# main.net
KiCad netlist of a schematic drawn in Altium Designer
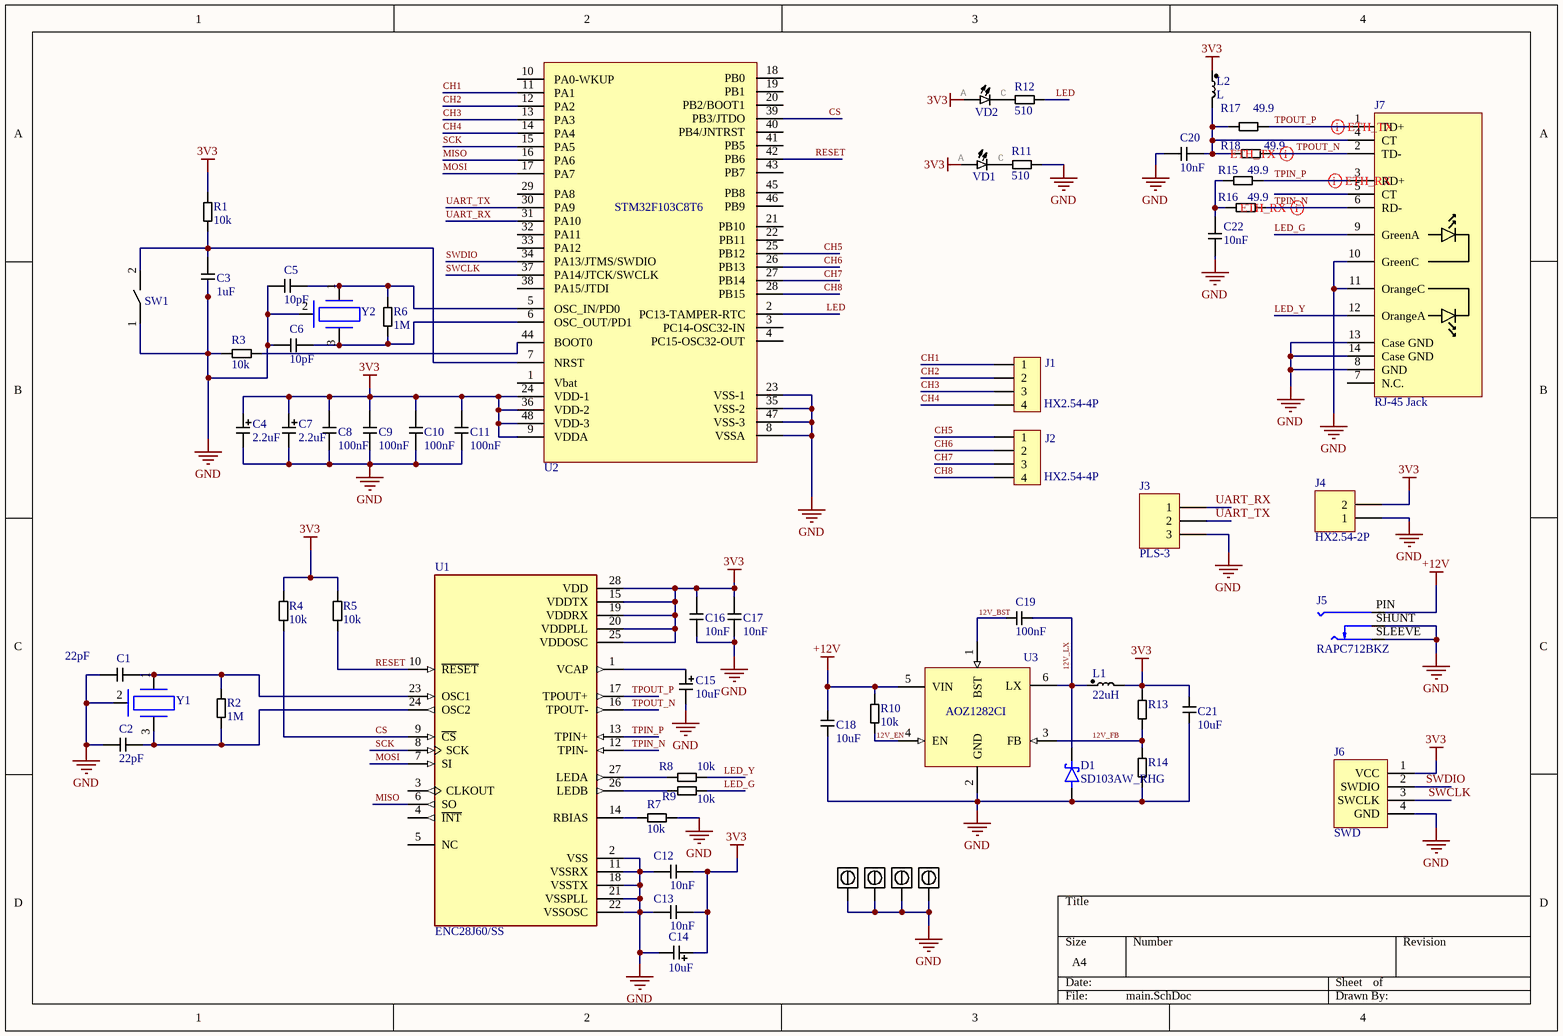
[diagram p0: main.SchDoc]

(export (version "E")
  (design (tool "Eeschema 10.0.6"))
  (components
    (comp (ref "1")
      (value "SMTSO_STAND_M3")
      (footprint "M3x1")
      (libsource (lib "SMTSO") (part "SMTSO_STAND_M3"))
    )
    (comp (ref "2")
      (value "SMTSO_STAND_M3")
      (footprint "M3x1")
      (libsource (lib "SMTSO") (part "SMTSO_STAND_M3"))
    )
    (comp (ref "3")
      (value "SMTSO_STAND_M3")
      (footprint "M3x1")
      (libsource (lib "SMTSO") (part "SMTSO_STAND_M3"))
    )
    (comp (ref "4")
      (value "SMTSO_STAND_M3")
      (footprint "M3x1")
      (libsource (lib "SMTSO") (part "SMTSO_STAND_M3"))
    )
    (comp (ref "C1")
      (value "22pF")
      (footprint "0805_MD_CAPC2012X05N")
      (description "Capacitor")
      (libsource (lib "") (part "C_1"))
    )
    (comp (ref "C2")
      (value "22pF")
      (footprint "0805_MD_CAPC2012X05N")
      (description "Capacitor")
      (libsource (lib "") (part "C_1"))
    )
    (comp (ref "C3")
      (value "1uF")
      (footprint "0805_MD_CAPC2012X05N")
      (description "Capacitor")
      (libsource (lib "") (part "C_1"))
    )
    (comp (ref "C4")
      (value "2.2uF")
      (footprint "6.3x5.4_HD_CAPAE7266X54L")
      (description "Capacitors IPC")
      (libsource (lib "Passive") (part "CP"))
    )
    (comp (ref "C5")
      (value "10pF")
      (footprint "0805_MD_CAPC2012X05N")
      (description "Capacitor")
      (libsource (lib "") (part "C_1"))
    )
    (comp (ref "C6")
      (value "10pF")
      (footprint "0805_MD_CAPC2012X05N")
      (description "Capacitor")
      (libsource (lib "") (part "C_1"))
    )
    (comp (ref "C7")
      (value "2.2uF")
      (footprint "6.3x5.4_HD_CAPAE7266X54L")
      (description "Capacitors IPC")
      (libsource (lib "Passive") (part "CP"))
    )
    (comp (ref "C8")
      (value "100nF")
      (footprint "0805_MD_CAPC2012X05N")
      (description "Capacitor")
      (libsource (lib "") (part "C_1"))
    )
    (comp (ref "C9")
      (value "100nF")
      (footprint "0805_MD_CAPC2012X05N")
      (description "Capacitor")
      (libsource (lib "") (part "C_1"))
    )
    (comp (ref "C10")
      (value "100nF")
      (footprint "0805_MD_CAPC2012X05N")
      (description "Capacitor")
      (libsource (lib "") (part "C_1"))
    )
    (comp (ref "C11")
      (value "100nF")
      (footprint "0805_MD_CAPC2012X05N")
      (description "Capacitor")
      (libsource (lib "") (part "C_1"))
    )
    (comp (ref "C12")
      (value "10nF")
      (footprint "0805_MD_CAPC2012X05N")
      (description "Capacitor")
      (libsource (lib "") (part "C_1"))
    )
    (comp (ref "C13")
      (value "10nF")
      (footprint "0805_MD_CAPC2012X05N")
      (description "Capacitor")
      (libsource (lib "") (part "C_1"))
    )
    (comp (ref "C14")
      (value "10uF")
      (footprint "6.3x5.4_HD_CAPAE7266X54L")
      (description "Capacitors IPC")
      (libsource (lib "Passive") (part "CP"))
    )
    (comp (ref "C15")
      (value "10uF")
      (footprint "6.3x5.4_HD_CAPAE7266X54L")
      (description "Capacitors IPC")
      (libsource (lib "Passive") (part "CP"))
    )
    (comp (ref "C16")
      (value "10nF")
      (footprint "0805_MD_CAPC2012X05N")
      (description "Capacitor")
      (libsource (lib "") (part "C_1"))
    )
    (comp (ref "C17")
      (value "10nF")
      (footprint "0805_MD_CAPC2012X05N")
      (description "Capacitor")
      (libsource (lib "") (part "C_1"))
    )
    (comp (ref "C18")
      (value "10uF")
      (footprint "0805_MD_CAPC2012X05N")
      (description "Capacitors IPC")
      (libsource (lib "Passive") (part "C"))
    )
    (comp (ref "C19")
      (value "100nF")
      (footprint "0805_MD_CAPC2012X05N")
      (description "Capacitors IPC")
      (libsource (lib "Passive") (part "C"))
    )
    (comp (ref "C20")
      (value "10nF")
      (footprint "0805_MD_CAPC2012X05N")
      (description "Capacitor")
      (libsource (lib "") (part "C_1"))
    )
    (comp (ref "C21")
      (value "10uF")
      (footprint "0805_MD_CAPC2012X05N")
      (description "Capacitors IPC")
      (libsource (lib "Passive") (part "C"))
    )
    (comp (ref "C22")
      (value "10nF")
      (footprint "0805_MD_CAPC2012X05N")
      (description "Capacitor")
      (libsource (lib "") (part "C_1"))
    )
    (comp (ref "D1")
      (value "SD103AW_RHG")
      (footprint "DIO_SD103AW_RHG")
      (libsource (lib "SD103AW_RHG") (part "SD103AW_RHG"))
    )
    (comp (ref "J1")
      (value "HX2.54-4P")
      (footprint "JST_S4B-XH-A(LF)(SN)")
      (description "JST HX 2.54 4P")
      (libsource (lib "Connector") (part "HX2.54-4P"))
    )
    (comp (ref "J2")
      (value "HX2.54-4P")
      (footprint "JST_S4B-XH-A(LF)(SN)")
      (description "JST HX 2.54 4P")
      (libsource (lib "Connector") (part "HX2.54-4P"))
    )
    (comp (ref "J3") (value "PLS-3") (footprint "PLS-1-3") (libsource (lib "Connector") (part "PLS-3")))
    (comp (ref "J4")
      (value "HX2.54-2P")
      (footprint "JST_S2B-XH-A(LF)(SN)")
      (description "JST HX 2.54 2P")
      (libsource (lib "Connector") (part "HX2.54-2P"))
    )
    (comp (ref "J5")
      (value "RAPC712BKZ")
      (footprint "SWITCHCRAFT_RAPC712BKZ")
      (description "Power Barrel Connector Jack 2.50mm ID (0.098), 5.50mm OD (0.217) Through Hole, Right Angle")
      (fields (field (name "MF") "Switchcraft Conxall"))
      (libsource (lib "RAPC712BKZ") (part "RAPC712BKZ"))
    )
    (comp (ref "J6")
      (value "SWD")
      (footprint "SWD-4")
      (description "SWD connector")
      (libsource (lib "Connector") (part "SWD_4"))
    )
    (comp (ref "J7")
      (value "RJ-45 Jack")
      (footprint "J011D21BNL")
      (description "Ethernet jack")
      (libsource (lib "Connector") (part "RJ-45 Jack"))
    )
    (comp (ref "L1")
      (value "22uH")
      (footprint "LQH32P_MD_INDP3225X17N")
      (description "Inductor IPC")
      (libsource (lib "Passive") (part "L"))
    )
    (comp (ref "L2")
      (value "L")
      (footprint "0603_LD_RESC1608X06M")
      (description "Inductor IPC")
      (libsource (lib "Passive") (part "L"))
    )
    (comp (ref "R1")
      (value "10k")
      (footprint "0805_MD_RESC2012X06N")
      (description "Resistor")
      (libsource (lib "") (part "R_1"))
    )
    (comp (ref "R2")
      (value "1M")
      (footprint "0805_MD_RESC2012X06N")
      (description "Resistor")
      (libsource (lib "") (part "R_1"))
    )
    (comp (ref "R3")
      (value "10k")
      (footprint "0805_MD_RESC2012X06N")
      (description "Resistor")
      (libsource (lib "") (part "R_1"))
    )
    (comp (ref "R4")
      (value "10k")
      (footprint "0805_MD_RESC2012X06N")
      (description "Resistors IPC")
      (libsource (lib "Passive") (part "R"))
    )
    (comp (ref "R5")
      (value "10k")
      (footprint "0805_MD_RESC2012X06N")
      (description "Resistors IPC")
      (libsource (lib "Passive") (part "R"))
    )
    (comp (ref "R6")
      (value "1M")
      (footprint "0805_MD_RESC2012X06N")
      (description "Resistor")
      (libsource (lib "") (part "R_1"))
    )
    (comp (ref "R7")
      (value "10k")
      (footprint "0805_MD_RESC2012X06N")
      (description "Resistors IPC")
      (libsource (lib "Passive") (part "R"))
    )
    (comp (ref "R8")
      (value "10k")
      (footprint "0805_MD_RESC2012X06N")
      (description "Resistors IPC")
      (libsource (lib "Passive") (part "R"))
    )
    (comp (ref "R9")
      (value "10k")
      (footprint "0805_MD_RESC2012X06N")
      (description "Resistors IPC")
      (libsource (lib "Passive") (part "R"))
    )
    (comp (ref "R10")
      (value "10k")
      (footprint "0805_MD_RESC2012X06N")
      (description "Resistors IPC")
      (libsource (lib "Passive") (part "R"))
    )
    (comp (ref "R11")
      (value "510")
      (footprint "0805_MD_RESC2012X06N")
      (description "Resistor")
      (libsource (lib "") (part "R_1"))
    )
    (comp (ref "R12")
      (value "510")
      (footprint "0805_MD_RESC2012X06N")
      (description "Resistor")
      (libsource (lib "") (part "R_1"))
    )
    (comp (ref "R13")
      (value "~")
      (footprint "0805_MD_RESC2012X06N")
      (description "Resistors IPC")
      (libsource (lib "Passive") (part "R"))
    )
    (comp (ref "R14")
      (value "~")
      (footprint "0805_MD_RESC2012X06N")
      (description "Resistors IPC")
      (libsource (lib "Passive") (part "R"))
    )
    (comp (ref "R15")
      (value "49.9")
      (footprint "0805_MD_RESC2012X06N")
      (description "Resistors IPC")
      (libsource (lib "Passive") (part "R"))
    )
    (comp (ref "R16")
      (value "49.9")
      (footprint "0805_MD_RESC2012X06N")
      (description "Resistors IPC")
      (libsource (lib "Passive") (part "R"))
    )
    (comp (ref "R17")
      (value "49.9")
      (footprint "0805_MD_RESC2012X06N")
      (description "Resistors IPC")
      (libsource (lib "Passive") (part "R"))
    )
    (comp (ref "R18")
      (value "49.9")
      (footprint "0805_MD_RESC2012X06N")
      (description "Resistors IPC")
      (libsource (lib "Passive") (part "R"))
    )
    (comp (ref "SW1") (value "LL3301") (footprint "LL3301") (libsource (lib "Buttons") (part "LL3301")))
    (comp (ref "U1")
      (value "ENC28J60/SS")
      (footprint "SOP65P780X200-28N")
      (description "28 Pin, 8 KB RAM, MAC&PHY, Ethernet Controller ¦ Microchip Technology Inc. ENC28J60/SS")
      (fields (field (name "MF") "Microchip"))
      (libsource (lib "ENC28J60_SS") (part "ENC28J60/SS"))
    )
    (comp (ref "U2")
      (value "GD32F103C8T6")
      (footprint "QFP48_MD_TSQFP50P900X900X120-48N")
      (libsource (lib "MCU") (part "STM32F103C8T6"))
    )
    (comp (ref "U3")
      (value "AOZ1282CI")
      (footprint "SOT23_6_MD_SOT95P280X125-6N")
      (fields (field (name "MANUFACTURER") "Alpha & Omega"))
      (libsource (lib "DC-DC IC") (part "AOZ1282CI"))
    )
    (comp (ref "VD1") (value "LED") (footprint "LEDSC125X200X90-2N") (libsource (lib "Diodes") (part "LED")))
    (comp (ref "VD2") (value "LED") (footprint "LED_APT2012MGC") (libsource (lib "Diodes") (part "LED")))
    (comp (ref "Y1")
      (value "3225")
      (footprint "YANGXING_SMD_3225_4L")
      (libsource (lib "Crystal Oscillator") (part "3225"))
    )
    (comp (ref "Y2")
      (value "X32258MOB4SI")
      (footprint "YANGXING_SMD_3225_4L")
      (description "Резонатор кварцевый 8MHz, ±10ppm... ±30ppm, 12пФ, SMD3225, -40...+85C")
      (libsource (lib "Crystal Oscillator") (part "3225"))
    )
  )
  (nets
    (net (code "1") (name "+12V") (class "Default")
      (node (ref "C18") (pin "1") (pinfunction "1_1") (pintype "passive"))
      (node (ref "J5") (pin "PIN") (pinfunction "PIN_PIN") (pintype "passive"))
      (node (ref "R10") (pin "2") (pinfunction "2_2") (pintype "passive"))
      (node (ref "U3") (pin "5") (pinfunction "VIN_5") (pintype "power_in"))
    )
    (net (code "2") (name "/12V_BST") (class "Default")
      (node (ref "C19") (pin "1") (pinfunction "1_1") (pintype "passive"))
      (node (ref "U3") (pin "1") (pinfunction "BST_1") (pintype "input"))
    )
    (net (code "3") (name "/12V_EN") (class "Default")
      (node (ref "R10") (pin "1") (pinfunction "1_1") (pintype "passive"))
      (node (ref "U3") (pin "4") (pinfunction "EN_4") (pintype "input"))
    )
    (net (code "4") (name "/12V_FB") (class "Default")
      (node (ref "R13") (pin "1") (pinfunction "1_1") (pintype "passive"))
      (node (ref "R14") (pin "2") (pinfunction "2_2") (pintype "passive"))
      (node (ref "U3") (pin "3") (pinfunction "FB_3") (pintype "input"))
    )
    (net (code "5") (name "/12V_LX") (class "Default")
      (node (ref "C19") (pin "2") (pinfunction "2_2") (pintype "passive"))
      (node (ref "D1") (pin "C") (pinfunction "K_C") (pintype "passive"))
      (node (ref "L1") (pin "1") (pinfunction "1_1") (pintype "passive"))
      (node (ref "U3") (pin "6") (pinfunction "LX_6") (pintype "power_in"))
    )
    (net (code "6") (name "/CH1") (class "Default")
      (node (ref "J1") (pin "1") (pinfunction "1_1") (pintype "passive"))
      (node (ref "U2") (pin "11") (pinfunction "PA1_11") (pintype "passive"))
    )
    (net (code "7") (name "/CH2") (class "Default")
      (node (ref "J1") (pin "2") (pinfunction "2_2") (pintype "passive"))
      (node (ref "U2") (pin "12") (pinfunction "PA2_12") (pintype "passive"))
    )
    (net (code "8") (name "/CH3") (class "Default")
      (node (ref "J1") (pin "3") (pinfunction "3_3") (pintype "passive"))
      (node (ref "U2") (pin "13") (pinfunction "PA3_13") (pintype "passive"))
    )
    (net (code "9") (name "/CH4") (class "Default")
      (node (ref "J1") (pin "4") (pinfunction "4_4") (pintype "passive"))
      (node (ref "U2") (pin "14") (pinfunction "PA4_14") (pintype "passive"))
    )
    (net (code "10") (name "/CH5") (class "Default")
      (node (ref "J2") (pin "1") (pinfunction "1_1") (pintype "passive"))
      (node (ref "U2") (pin "25") (pinfunction "PB12_25") (pintype "passive"))
    )
    (net (code "11") (name "/CH6") (class "Default")
      (node (ref "J2") (pin "2") (pinfunction "2_2") (pintype "passive"))
      (node (ref "U2") (pin "26") (pinfunction "PB13_26") (pintype "passive"))
    )
    (net (code "12") (name "/CH7") (class "Default")
      (node (ref "J2") (pin "3") (pinfunction "3_3") (pintype "passive"))
      (node (ref "U2") (pin "27") (pinfunction "PB14_27") (pintype "passive"))
    )
    (net (code "13") (name "/CH8") (class "Default")
      (node (ref "J2") (pin "4") (pinfunction "4_4") (pintype "passive"))
      (node (ref "U2") (pin "28") (pinfunction "PB15_28") (pintype "passive"))
    )
    (net (code "14") (name "/CS") (class "Default")
      (node (ref "R4") (pin "1") (pinfunction "1_1") (pintype "passive"))
      (node (ref "U1") (pin "9") (pinfunction "~{CS}_9") (pintype "input"))
      (node (ref "U2") (pin "39") (pinfunction "PB3/JTDO_39") (pintype "passive"))
    )
    (net (code "15") (name "/LED") (class "Default")
      (node (ref "R12") (pin "2") (pinfunction "2_2") (pintype "passive"))
      (node (ref "U2") (pin "2") (pinfunction "PC13-TAMPER-RTC_2") (pintype "passive"))
    )
    (net (code "16") (name "/LED_G") (class "Default")
      (node (ref "J7") (pin "9") (pinfunction "GreenA_9") (pintype "passive"))
      (node (ref "R9") (pin "1") (pinfunction "1_1") (pintype "passive"))
    )
    (net (code "17") (name "/LED_Y") (class "Default")
      (node (ref "J7") (pin "12") (pinfunction "OrangeA_12") (pintype "passive"))
      (node (ref "R8") (pin "1") (pinfunction "1_1") (pintype "passive"))
    )
    (net (code "18") (name "/MISO") (class "Default")
      (node (ref "U1") (pin "6") (pinfunction "SO_6") (pintype "output"))
      (node (ref "U2") (pin "16") (pinfunction "PA6_16") (pintype "passive"))
    )
    (net (code "19") (name "/MOSI") (class "Default")
      (node (ref "U1") (pin "7") (pinfunction "SI_7") (pintype "input"))
      (node (ref "U2") (pin "17") (pinfunction "PA7_17") (pintype "passive"))
    )
    (net (code "20") (name "/RESET") (class "Default")
      (node (ref "R5") (pin "1") (pinfunction "1_1") (pintype "passive"))
      (node (ref "U1") (pin "10") (pinfunction "~{RESET}_10") (pintype "input"))
      (node (ref "U2") (pin "42") (pinfunction "PB6_42") (pintype "passive"))
    )
    (net (code "21") (name "/SCK") (class "Default")
      (node (ref "U1") (pin "8") (pinfunction "SCK_8") (pintype "input"))
      (node (ref "U2") (pin "15") (pinfunction "PA5_15") (pintype "passive"))
    )
    (net (code "22") (name "/SWCLK") (class "Default")
      (node (ref "J6") (pin "3") (pinfunction "SWCLK_3") (pintype "passive"))
      (node (ref "U2") (pin "37") (pinfunction "PA14/JTCK/SWCLK_37") (pintype "passive"))
    )
    (net (code "23") (name "/SWDIO") (class "Default")
      (node (ref "J6") (pin "2") (pinfunction "SWDIO_2") (pintype "passive"))
      (node (ref "U2") (pin "34") (pinfunction "PA13/JTMS/SWDIO_34") (pintype "passive"))
    )
    (net (code "24") (name "/TPIN_N") (class "Default")
      (node (ref "J7") (pin "6") (pinfunction "RD-_6") (pintype "passive"))
      (node (ref "R16") (pin "1") (pinfunction "1_1") (pintype "passive"))
      (node (ref "U1") (pin "12") (pinfunction "TPIN-_12") (pintype "input"))
    )
    (net (code "25") (name "/TPIN_P") (class "Default")
      (node (ref "J7") (pin "3") (pinfunction "RD+_3") (pintype "passive"))
      (node (ref "R15") (pin "1") (pinfunction "1_1") (pintype "passive"))
      (node (ref "U1") (pin "13") (pinfunction "TPIN+_13") (pintype "input"))
    )
    (net (code "26") (name "/TPOUT_N") (class "Default")
      (node (ref "J7") (pin "2") (pinfunction "TD-_2") (pintype "passive"))
      (node (ref "R18") (pin "1") (pinfunction "1_1") (pintype "passive"))
      (node (ref "U1") (pin "16") (pinfunction "TPOUT-_16") (pintype "output"))
    )
    (net (code "27") (name "/TPOUT_P") (class "Default")
      (node (ref "J7") (pin "1") (pinfunction "TD+_1") (pintype "passive"))
      (node (ref "R17") (pin "1") (pinfunction "1_1") (pintype "passive"))
      (node (ref "U1") (pin "17") (pinfunction "TPOUT+_17") (pintype "output"))
    )
    (net (code "28") (name "/UART_RX") (class "Default")
      (node (ref "J3") (pin "1") (pinfunction "1_1") (pintype "passive"))
      (node (ref "U2") (pin "31") (pinfunction "PA10_31") (pintype "passive"))
    )
    (net (code "29") (name "/UART_TX") (class "Default")
      (node (ref "J3") (pin "2") (pinfunction "2_2") (pintype "passive"))
      (node (ref "U2") (pin "30") (pinfunction "PA9_30") (pintype "passive"))
    )
    (net (code "30") (name "3V3") (class "Default")
      (node (ref "C10") (pin "1") (pinfunction "1_1") (pintype "passive"))
      (node (ref "C11") (pin "1") (pinfunction "1_1") (pintype "passive"))
      (node (ref "C12") (pin "2") (pinfunction "2_2") (pintype "passive"))
      (node (ref "C13") (pin "2") (pinfunction "2_2") (pintype "passive"))
      (node (ref "C14") (pin "1") (pinfunction "1_1") (pintype "passive"))
      (node (ref "C16") (pin "1") (pinfunction "1_1") (pintype "passive"))
      (node (ref "C17") (pin "1") (pinfunction "1_1") (pintype "passive"))
      (node (ref "C21") (pin "1") (pinfunction "1_1") (pintype "passive"))
      (node (ref "C4") (pin "1") (pinfunction "1_1") (pintype "passive"))
      (node (ref "C7") (pin "1") (pinfunction "1_1") (pintype "passive"))
      (node (ref "C8") (pin "1") (pinfunction "1_1") (pintype "passive"))
      (node (ref "C9") (pin "1") (pinfunction "1_1") (pintype "passive"))
      (node (ref "J4") (pin "2") (pinfunction "2_2") (pintype "passive"))
      (node (ref "J6") (pin "1") (pinfunction "VCC_1") (pintype "passive"))
      (node (ref "L1") (pin "2") (pinfunction "2_2") (pintype "passive"))
      (node (ref "L2") (pin "1") (pinfunction "1_1") (pintype "passive"))
      (node (ref "R1") (pin "2") (pinfunction "2_2") (pintype "passive"))
      (node (ref "R13") (pin "2") (pinfunction "2_2") (pintype "passive"))
      (node (ref "R4") (pin "2") (pinfunction "2_2") (pintype "passive"))
      (node (ref "R5") (pin "2") (pinfunction "2_2") (pintype "passive"))
      (node (ref "U1") (pin "15") (pinfunction "VDDTX_15") (pintype "power_in"))
      (node (ref "U1") (pin "19") (pinfunction "VDDRX_19") (pintype "power_in"))
      (node (ref "U1") (pin "20") (pinfunction "VDDPLL_20") (pintype "power_in"))
      (node (ref "U1") (pin "25") (pinfunction "VDDOSC_25") (pintype "power_in"))
      (node (ref "U1") (pin "28") (pinfunction "VDD_28") (pintype "power_in"))
      (node (ref "U2") (pin "24") (pinfunction "VDD-1_24") (pintype "passive"))
      (node (ref "U2") (pin "36") (pinfunction "VDD-2_36") (pintype "passive"))
      (node (ref "U2") (pin "48") (pinfunction "VDD-3_48") (pintype "passive"))
      (node (ref "U2") (pin "9") (pinfunction "VDDA_9") (pintype "passive"))
      (node (ref "VD1") (pin "A") (pinfunction "A_A") (pintype "passive"))
      (node (ref "VD2") (pin "A") (pinfunction "A_A") (pintype "passive"))
    )
    (net (code "31") (name "GND") (class "Default")
      (node (ref "1") (pin "1") (pinfunction "1_1") (pintype "passive"))
      (node (ref "2") (pin "1") (pinfunction "1_1") (pintype "passive"))
      (node (ref "3") (pin "1") (pinfunction "1_1") (pintype "passive"))
      (node (ref "4") (pin "1") (pinfunction "1_1") (pintype "passive"))
      (node (ref "C1") (pin "1") (pinfunction "1_1") (pintype "passive"))
      (node (ref "C10") (pin "2") (pinfunction "2_2") (pintype "passive"))
      (node (ref "C11") (pin "2") (pinfunction "2_2") (pintype "passive"))
      (node (ref "C12") (pin "1") (pinfunction "1_1") (pintype "passive"))
      (node (ref "C13") (pin "1") (pinfunction "1_1") (pintype "passive"))
      (node (ref "C14") (pin "2") (pinfunction "2_2") (pintype "passive"))
      (node (ref "C15") (pin "2") (pinfunction "2_2") (pintype "passive"))
      (node (ref "C16") (pin "2") (pinfunction "2_2") (pintype "passive"))
      (node (ref "C17") (pin "2") (pinfunction "2_2") (pintype "passive"))
      (node (ref "C18") (pin "2") (pinfunction "2_2") (pintype "passive"))
      (node (ref "C2") (pin "1") (pinfunction "1_1") (pintype "passive"))
      (node (ref "C20") (pin "2") (pinfunction "2_2") (pintype "passive"))
      (node (ref "C21") (pin "2") (pinfunction "2_2") (pintype "passive"))
      (node (ref "C22") (pin "2") (pinfunction "2_2") (pintype "passive"))
      (node (ref "C3") (pin "2") (pinfunction "2_2") (pintype "passive"))
      (node (ref "C4") (pin "2") (pinfunction "2_2") (pintype "passive"))
      (node (ref "C5") (pin "1") (pinfunction "1_1") (pintype "passive"))
      (node (ref "C6") (pin "1") (pinfunction "1_1") (pintype "passive"))
      (node (ref "C7") (pin "2") (pinfunction "2_2") (pintype "passive"))
      (node (ref "C8") (pin "2") (pinfunction "2_2") (pintype "passive"))
      (node (ref "C9") (pin "2") (pinfunction "2_2") (pintype "passive"))
      (node (ref "D1") (pin "A") (pinfunction "A_A") (pintype "passive"))
      (node (ref "J3") (pin "3") (pinfunction "3_3") (pintype "passive"))
      (node (ref "J4") (pin "1") (pinfunction "1_1") (pintype "passive"))
      (node (ref "J5") (pin "SHUNT") (pinfunction "SHUNT_SHUNT") (pintype "passive"))
      (node (ref "J5") (pin "SLEEVE") (pinfunction "SLEEVE_SLEEVE") (pintype "passive"))
      (node (ref "J6") (pin "4") (pinfunction "GND_4") (pintype "passive"))
      (node (ref "J7") (pin "10") (pinfunction "GreenC_10") (pintype "passive"))
      (node (ref "J7") (pin "11") (pinfunction "OrangeC_11") (pintype "passive"))
      (node (ref "J7") (pin "13") (pinfunction "Case_GND_13") (pintype "passive"))
      (node (ref "J7") (pin "14") (pinfunction "Case_GND_14") (pintype "passive"))
      (node (ref "J7") (pin "8") (pinfunction "GND_8") (pintype "passive"))
      (node (ref "R11") (pin "2") (pinfunction "2_2") (pintype "passive"))
      (node (ref "R14") (pin "1") (pinfunction "1_1") (pintype "passive"))
      (node (ref "R3") (pin "1") (pinfunction "1_1") (pintype "passive"))
      (node (ref "R7") (pin "1") (pinfunction "1_1") (pintype "passive"))
      (node (ref "SW1") (pin "1") (pinfunction "1_1") (pintype "passive"))
      (node (ref "U1") (pin "11") (pinfunction "VSSRX_11") (pintype "power_in"))
      (node (ref "U1") (pin "18") (pinfunction "VSSTX_18") (pintype "power_in"))
      (node (ref "U1") (pin "2") (pinfunction "VSS_2") (pintype "power_in"))
      (node (ref "U1") (pin "21") (pinfunction "VSSPLL_21") (pintype "power_in"))
      (node (ref "U1") (pin "22") (pinfunction "VSSOSC_22") (pintype "power_in"))
      (node (ref "U2") (pin "23") (pinfunction "VSS-1_23") (pintype "passive"))
      (node (ref "U2") (pin "35") (pinfunction "VSS-2_35") (pintype "passive"))
      (node (ref "U2") (pin "47") (pinfunction "VSS-3_47") (pintype "passive"))
      (node (ref "U2") (pin "8") (pinfunction "VSSA_8") (pintype "passive"))
      (node (ref "U3") (pin "2") (pinfunction "GND_2") (pintype "power_in"))
      (node (ref "Y1") (pin "2") (pinfunction "GND_2") (pintype "passive"))
      (node (ref "Y2") (pin "2") (pinfunction "GND_2") (pintype "passive"))
    )
    (net (code "32") (name "Net-(C20-Pad1)") (class "Default")
      (node (ref "C20") (pin "1") (pinfunction "1_1") (pintype "passive"))
      (node (ref "J7") (pin "4") (pinfunction "CT_4") (pintype "passive"))
      (node (ref "L2") (pin "2") (pinfunction "2_2") (pintype "passive"))
      (node (ref "R17") (pin "2") (pinfunction "2_2") (pintype "passive"))
      (node (ref "R18") (pin "2") (pinfunction "2_2") (pintype "passive"))
    )
    (net (code "33") (name "Net-(C22-Pad1)") (class "Default")
      (node (ref "C22") (pin "1") (pinfunction "1_1") (pintype "passive"))
      (node (ref "R15") (pin "2") (pinfunction "2_2") (pintype "passive"))
      (node (ref "R16") (pin "2") (pinfunction "2_2") (pintype "passive"))
    )
    (net (code "34") (name "Net-(R11-Pad1)") (class "Default")
      (node (ref "R11") (pin "1") (pinfunction "1_1") (pintype "passive"))
      (node (ref "VD1") (pin "C") (pinfunction "C_C") (pintype "passive"))
    )
    (net (code "35") (name "Net-(R12-Pad1)") (class "Default")
      (node (ref "R12") (pin "1") (pinfunction "1_1") (pintype "passive"))
      (node (ref "VD2") (pin "C") (pinfunction "C_C") (pintype "passive"))
    )
    (net (code "36") (name "Net-(U1-LEDA)") (class "Default")
      (node (ref "R8") (pin "2") (pinfunction "2_2") (pintype "passive"))
      (node (ref "U1") (pin "27") (pinfunction "LEDA_27") (pintype "output"))
    )
    (net (code "37") (name "Net-(U1-LEDB)") (class "Default")
      (node (ref "R9") (pin "2") (pinfunction "2_2") (pintype "passive"))
      (node (ref "U1") (pin "26") (pinfunction "LEDB_26") (pintype "output"))
    )
    (net (code "38") (name "Net-(U1-OSC1)") (class "Default")
      (node (ref "C1") (pin "2") (pinfunction "2_2") (pintype "passive"))
      (node (ref "R2") (pin "2") (pinfunction "2_2") (pintype "passive"))
      (node (ref "U1") (pin "23") (pinfunction "OSC1_23") (pintype "input"))
      (node (ref "Y1") (pin "1") (pinfunction "IN_1") (pintype "passive"))
    )
    (net (code "39") (name "Net-(U1-OSC2)") (class "Default")
      (node (ref "C2") (pin "2") (pinfunction "2_2") (pintype "passive"))
      (node (ref "R2") (pin "1") (pinfunction "1_1") (pintype "passive"))
      (node (ref "U1") (pin "24") (pinfunction "OSC2_24") (pintype "output"))
      (node (ref "Y1") (pin "3") (pinfunction "OUT_3") (pintype "passive"))
    )
    (net (code "40") (name "Net-(U1-RBIAS)") (class "Default")
      (node (ref "R7") (pin "2") (pinfunction "2_2") (pintype "passive"))
      (node (ref "U1") (pin "14") (pinfunction "RBIAS_14") (pintype "passive"))
    )
    (net (code "41") (name "Net-(U1-VCAP)") (class "Default")
      (node (ref "C15") (pin "1") (pinfunction "1_1") (pintype "passive"))
      (node (ref "U1") (pin "1") (pinfunction "VCAP_1") (pintype "output"))
    )
    (net (code "42") (name "Net-(U2-BOOT0)") (class "Default")
      (node (ref "R3") (pin "2") (pinfunction "2_2") (pintype "passive"))
      (node (ref "U2") (pin "44") (pinfunction "BOOT0_44") (pintype "passive"))
    )
    (net (code "43") (name "Net-(U2-NRST)") (class "Default")
      (node (ref "C3") (pin "1") (pinfunction "1_1") (pintype "passive"))
      (node (ref "R1") (pin "1") (pinfunction "1_1") (pintype "passive"))
      (node (ref "SW1") (pin "2") (pinfunction "2_2") (pintype "passive"))
      (node (ref "U2") (pin "7") (pinfunction "NRST_7") (pintype "passive"))
    )
    (net (code "44") (name "Net-(U2-OSC_IN{slash}PD0)") (class "Default")
      (node (ref "C5") (pin "2") (pinfunction "2_2") (pintype "passive"))
      (node (ref "R6") (pin "2") (pinfunction "2_2") (pintype "passive"))
      (node (ref "U2") (pin "5") (pinfunction "OSC_IN/PD0_5") (pintype "passive"))
      (node (ref "Y2") (pin "1") (pinfunction "IN_1") (pintype "passive"))
    )
    (net (code "45") (name "Net-(U2-OSC_OUT{slash}PD1)") (class "Default")
      (node (ref "C6") (pin "2") (pinfunction "2_2") (pintype "passive"))
      (node (ref "R6") (pin "1") (pinfunction "1_1") (pintype "passive"))
      (node (ref "U2") (pin "6") (pinfunction "OSC_OUT/PD1_6") (pintype "passive"))
      (node (ref "Y2") (pin "3") (pinfunction "OUT_3") (pintype "passive"))
    )
    (net (code "46") (name "unconnected-(J7-CT-Pad5)") (class "Default")
      (node (ref "J7") (pin "5") (pinfunction "CT_5") (pintype "passive"))
    )
    (net (code "47") (name "unconnected-(J7-N.C.-Pad7)") (class "Default")
      (node (ref "J7") (pin "7") (pinfunction "N.C._7") (pintype "passive"))
    )
    (net (code "48") (name "unconnected-(U1-CLKOUT-Pad3)") (class "Default")
      (node (ref "U1") (pin "3") (pinfunction "CLKOUT_3") (pintype "output"))
    )
    (net (code "49") (name "unconnected-(U1-NC-Pad5)") (class "Default")
      (node (ref "U1") (pin "5") (pinfunction "NC_5") (pintype "passive"))
    )
    (net (code "50") (name "unconnected-(U1-~{INT}-Pad4)") (class "Default")
      (node (ref "U1") (pin "4") (pinfunction "~{INT}_4") (pintype "output"))
    )
    (net (code "51") (name "unconnected-(U2-PA0-WKUP-Pad10)") (class "Default")
      (node (ref "U2") (pin "10") (pinfunction "PA0-WKUP_10") (pintype "passive"))
    )
    (net (code "52") (name "unconnected-(U2-PA8-Pad29)") (class "Default")
      (node (ref "U2") (pin "29") (pinfunction "PA8_29") (pintype "passive"))
    )
    (net (code "53") (name "unconnected-(U2-PA11-Pad32)") (class "Default")
      (node (ref "U2") (pin "32") (pinfunction "PA11_32") (pintype "passive"))
    )
    (net (code "54") (name "unconnected-(U2-PA12-Pad33)") (class "Default")
      (node (ref "U2") (pin "33") (pinfunction "PA12_33") (pintype "passive"))
    )
    (net (code "55") (name "unconnected-(U2-PA15{slash}JTDI-Pad38)") (class "Default")
      (node (ref "U2") (pin "38") (pinfunction "PA15/JTDI_38") (pintype "passive"))
    )
    (net (code "56") (name "unconnected-(U2-PB0-Pad18)") (class "Default")
      (node (ref "U2") (pin "18") (pinfunction "PB0_18") (pintype "passive"))
    )
    (net (code "57") (name "unconnected-(U2-PB1-Pad19)") (class "Default")
      (node (ref "U2") (pin "19") (pinfunction "PB1_19") (pintype "passive"))
    )
    (net (code "58") (name "unconnected-(U2-PB2{slash}BOOT1-Pad20)") (class "Default")
      (node (ref "U2") (pin "20") (pinfunction "PB2/BOOT1_20") (pintype "passive"))
    )
    (net (code "59") (name "unconnected-(U2-PB4{slash}JNTRST-Pad40)") (class "Default")
      (node (ref "U2") (pin "40") (pinfunction "PB4/JNTRST_40") (pintype "passive"))
    )
    (net (code "60") (name "unconnected-(U2-PB5-Pad41)") (class "Default")
      (node (ref "U2") (pin "41") (pinfunction "PB5_41") (pintype "passive"))
    )
    (net (code "61") (name "unconnected-(U2-PB7-Pad43)") (class "Default")
      (node (ref "U2") (pin "43") (pinfunction "PB7_43") (pintype "passive"))
    )
    (net (code "62") (name "unconnected-(U2-PB8-Pad45)") (class "Default")
      (node (ref "U2") (pin "45") (pinfunction "PB8_45") (pintype "passive"))
    )
    (net (code "63") (name "unconnected-(U2-PB9-Pad46)") (class "Default")
      (node (ref "U2") (pin "46") (pinfunction "PB9_46") (pintype "passive"))
    )
    (net (code "64") (name "unconnected-(U2-PB10-Pad21)") (class "Default")
      (node (ref "U2") (pin "21") (pinfunction "PB10_21") (pintype "passive"))
    )
    (net (code "65") (name "unconnected-(U2-PB11-Pad22)") (class "Default")
      (node (ref "U2") (pin "22") (pinfunction "PB11_22") (pintype "passive"))
    )
    (net (code "66") (name "unconnected-(U2-PC14-OSC32-IN-Pad3)") (class "Default")
      (node (ref "U2") (pin "3") (pinfunction "PC14-OSC32-IN_3") (pintype "passive"))
    )
    (net (code "67") (name "unconnected-(U2-PC15-OSC32-OUT-Pad4)") (class "Default")
      (node (ref "U2") (pin "4") (pinfunction "PC15-OSC32-OUT_4") (pintype "passive"))
    )
    (net (code "68") (name "unconnected-(U2-Vbat-Pad1)") (class "Default")
      (node (ref "U2") (pin "1") (pinfunction "Vbat_1") (pintype "passive"))
    )
  )
)
